# Power_Supply.net
KiCad netlist of a schematic drawn in Altium Designer
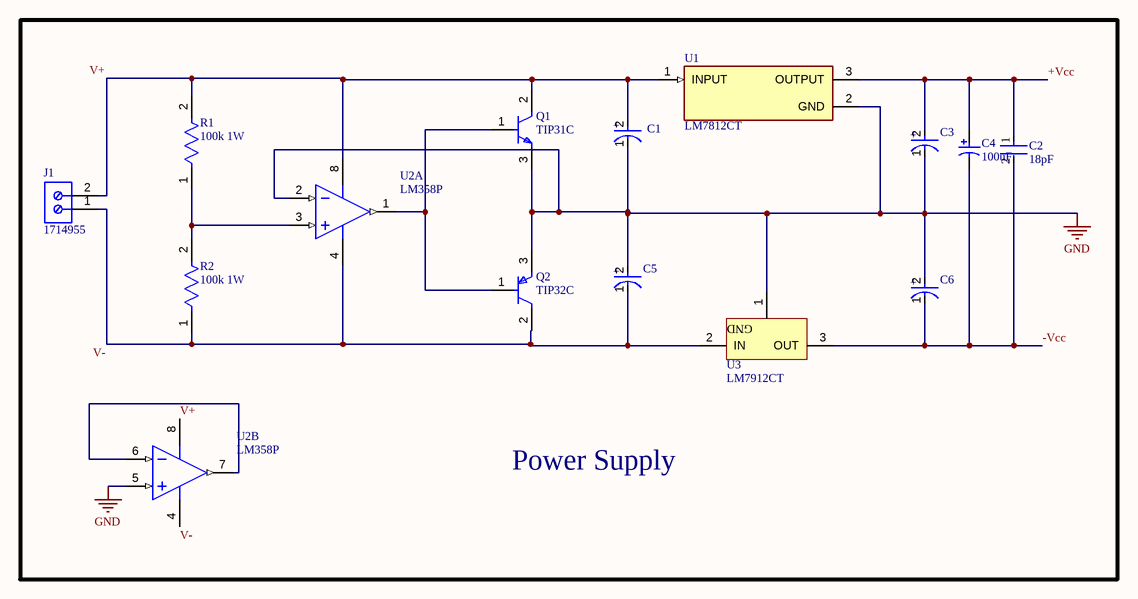
[diagram p0: Power_Supply.SchDoc]

(export (version "E")
  (design (tool "Eeschema 10.0.6"))
  (components
    (comp (ref "C1")
      (value "EEUFC1H4R7B")
      (footprint "FP-RAD-TH-D_5_0_5-L_11_1-MFG")
      (description "Aluminum Electrolytic Capacitors (Radial Lead Type) AEC-Q200 Qualified 4.7uF ±20% 50V")
      (fields (field (name "TOLERANCE") "20%"))
      (libsource (lib "Altium Content Vault") (part "a00bbbee19879c290e62620ae7e47b1"))
    )
    (comp (ref "C2")
      (value "18pF")
      (footprint "FP-F471K33Y5RP6UK5R-MFG")
      (description "CAP CER 470PF 2KV Y5R RADIAL")
      (fields (field (name "TOLERANCE") "10%") (field (name "VOLTAGE") "2kV"))
      (libsource (lib "Altium Content Vault") (part "b4654b650e69147ec39a6b967a45e02"))
    )
    (comp (ref "C3")
      (value "EEUFC1H4R7B")
      (footprint "FP-RAD-TH-D_5_0_5-L_11_1-MFG")
      (description "Aluminum Electrolytic Capacitors (Radial Lead Type) AEC-Q200 Qualified 4.7uF ±20% 50V")
      (fields (field (name "TOLERANCE") "20%"))
      (libsource (lib "Altium Content Vault") (part "a00bbbee19879c290e62620ae7e47b1"))
    )
    (comp (ref "C4")
      (value "100uF")
      (footprint "CAPPR65-350-1150X800X1250")
      (description "Aluminum Electrolytic Capacitor, 100 uF, +/- 20%, 50 V, -40 to 85 degC, 2-Pin THD, RoHS, Bulk")
      (fields (field (name "MANUFACTURER") "Panasonic") (field (name "VOLTAGE") "50V"))
      (libsource (lib "Altium Content Vault") (part "CAP-P-2"))
    )
    (comp (ref "C5")
      (value "EEUFC1H4R7B")
      (footprint "FP-RAD-TH-D_5_0_5-L_11_1-MFG")
      (description "Aluminum Electrolytic Capacitors (Radial Lead Type) AEC-Q200 Qualified 4.7uF ±20% 50V")
      (fields (field (name "TOLERANCE") "20%"))
      (libsource (lib "Altium Content Vault") (part "a00bbbee19879c290e62620ae7e47b1"))
    )
    (comp (ref "C6")
      (value "EEUFC1H4R7B")
      (footprint "FP-RAD-TH-D_5_0_5-L_11_1-MFG")
      (description "Aluminum Electrolytic Capacitors (Radial Lead Type) AEC-Q200 Qualified 4.7uF ±20% 50V")
      (fields (field (name "TOLERANCE") "20%"))
      (libsource (lib "Altium Content Vault") (part "a00bbbee19879c290e62620ae7e47b1"))
    )
    (comp (ref "J1")
      (value "1714955")
      (footprint "PHOE-1714955_V")
      (description "PC Terminal Block, Pitch 6.35 mm, 1 x 2 Position, Height 21.5 mm, Tail Lenght 5.1 mm, RoHS, Bulk")
      (fields (field (name "MANUFACTURER") "Phoenix Contact"))
      (libsource (lib "Altium Content Vault") (part "CN-1P-F-TB2"))
    )
    (comp (ref "Q1")
      (value "TIP31C")
      (footprint "FP-TO-220-P0A0015988-MFG")
      (description "TRANS NPN 100V 3A TO-220")
      (fields
        (field (name "OCTOPART") "https://octopart.com/tip31c-stmicroelectronics-15555")
        (field (name "MANUFACTURER") "STMicroelectronics")
      )
      (libsource (lib "Altium Content Vault") (part "1c57d9dae74fe2702546667b0e849db"))
    )
    (comp (ref "Q2")
      (value "TIP32C")
      (footprint "FP-TO-220-P0A0015988-MFG")
      (description "TRANS PNP 100V 3A TO-220")
      (fields
        (field (name "MANUFACTURER") "STMicroelectronics")
        (field (name "OCTOPART") "https://octopart.com/tip32c-stmicroelectronics-353617")
      )
      (libsource (lib "Altium Content Vault") (part "802a31d42ca070764d097f06bc9597f"))
    )
    (comp (ref "R1")
      (value "100k 1W")
      (footprint "FP-RR01-MFG")
      (description "RES 100K OHM 5% 1W AXIAL")
      (fields (field (name "TOLERANCE") "5%"))
      (libsource (lib "Altium Content Vault") (part "1029c3af85768c4190bb7ad29bc67b5"))
    )
    (comp (ref "R2")
      (value "100k 1W")
      (footprint "FP-RR01-MFG")
      (description "RES 100K OHM 5% 1W AXIAL")
      (fields (field (name "TOLERANCE") "5%"))
      (libsource (lib "Altium Content Vault") (part "1029c3af85768c4190bb7ad29bc67b5"))
    )
    (comp (ref "U1")
      (value "LM7812CT")
      (footprint "FP-TO220B03-MFG")
      (description "IC REG LINEAR 12V 1A TO220-3")
      (fields
        (field (name "OCTOPART") "https://octopart.com/lm7812ct-on+semiconductor-14383031")
        (field (name "OBSOLETE PART") "true")
      )
      (libsource (lib "Altium Content Vault") (part "6207a8f1a6b4db326a9e0a8a99b4969"))
    )
    (comp (ref "U2")
      (value "LM358P")
      (footprint "P0008A")
      (description "Dual Operational Amplifier, 3 to 32 V, 0 to 70 degC, 8-Pin PDIP (P), RoHS, Tape and Reel")
      (fields (field (name "MANUFACTURER") "Technik Industrial"))
      (libsource (lib "Altium Content Vault") (part "TI-LM_LPXXX-SO_DIP8"))
    )
    (comp (ref "U3")
      (value "LM7912CT")
      (footprint "NDE0003A")
      (description "3-Terminal Negative Regulator, 3-pin TO-220")
      (fields (field (name "MANUFACTURER") "Texas Instruments"))
      (libsource (lib "Altium Content Vault") (part "PM-REG-LM7905-SIL3"))
    )
  )
  (nets
    (net (code "1") (name "/+Vcc") (class "Default")
      (node (ref "C2") (pin "1") (pinfunction "1_1") (pintype "passive"))
      (node (ref "C3") (pin "2") (pinfunction "A_2") (pintype "passive"))
      (node (ref "C4") (pin "1") (pinfunction "1_1") (pintype "passive"))
      (node (ref "U1") (pin "3") (pinfunction "OUTPUT_3") (pintype "passive"))
    )
    (net (code "2") (name "/-Vcc") (class "Default")
      (node (ref "C2") (pin "2") (pinfunction "2_2") (pintype "passive"))
      (node (ref "C4") (pin "2") (pinfunction "2_2") (pintype "passive"))
      (node (ref "C6") (pin "1") (pinfunction "C_1") (pintype "passive"))
      (node (ref "U3") (pin "3") (pinfunction "OUT_3") (pintype "power_in"))
    )
    (net (code "3") (name "/V+") (class "Default")
      (node (ref "C1") (pin "2") (pinfunction "A_2") (pintype "passive"))
      (node (ref "J1") (pin "2") (pinfunction "2_2") (pintype "passive"))
      (node (ref "Q1") (pin "2") (pinfunction "C_2") (pintype "passive"))
      (node (ref "R1") (pin "2") (pinfunction "2_2") (pintype "passive"))
      (node (ref "U1") (pin "1") (pinfunction "INPUT_1") (pintype "input"))
      (node (ref "U2") (pin "8") (pinfunction "VCC_8") (pintype "power_in"))
    )
    (net (code "4") (name "/V-") (class "Default")
      (node (ref "C5") (pin "1") (pinfunction "C_1") (pintype "passive"))
      (node (ref "J1") (pin "1") (pinfunction "1_1") (pintype "passive"))
      (node (ref "Q2") (pin "2") (pinfunction "C_2") (pintype "passive"))
      (node (ref "R2") (pin "1") (pinfunction "1_1") (pintype "passive"))
      (node (ref "U2") (pin "4") (pinfunction "GND_4") (pintype "power_in"))
      (node (ref "U3") (pin "2") (pinfunction "IN_2") (pintype "power_in"))
    )
    (net (code "5") (name "GND") (class "Default")
      (node (ref "C1") (pin "1") (pinfunction "C_1") (pintype "passive"))
      (node (ref "C3") (pin "1") (pinfunction "C_1") (pintype "passive"))
      (node (ref "C5") (pin "2") (pinfunction "A_2") (pintype "passive"))
      (node (ref "C6") (pin "2") (pinfunction "A_2") (pintype "passive"))
      (node (ref "Q1") (pin "3") (pinfunction "E_3") (pintype "passive"))
      (node (ref "Q2") (pin "3") (pinfunction "E_3") (pintype "passive"))
      (node (ref "U1") (pin "2") (pinfunction "GND_2") (pintype "power_in"))
      (node (ref "U2") (pin "2") (pinfunction "1IN-_2") (pintype "input"))
      (node (ref "U2") (pin "5") (pinfunction "2IN+_5") (pintype "input"))
      (node (ref "U3") (pin "1") (pinfunction "GND_1") (pintype "power_in"))
    )
    (net (code "6") (name "Net-(Q1-B)") (class "Default")
      (node (ref "Q1") (pin "1") (pinfunction "B_1") (pintype "passive"))
      (node (ref "Q2") (pin "1") (pinfunction "B_1") (pintype "passive"))
      (node (ref "U2") (pin "1") (pinfunction "1OUT_1") (pintype "output"))
    )
    (net (code "7") (name "Net-(U2A-1IN+)") (class "Default")
      (node (ref "R1") (pin "1") (pinfunction "1_1") (pintype "passive"))
      (node (ref "R2") (pin "2") (pinfunction "2_2") (pintype "passive"))
      (node (ref "U2") (pin "3") (pinfunction "1IN+_3") (pintype "input"))
    )
    (net (code "8") (name "Net-(U2B-2IN-)") (class "Default")
      (node (ref "U2") (pin "6") (pinfunction "2IN-_6") (pintype "input"))
      (node (ref "U2") (pin "7") (pinfunction "2OUT_7") (pintype "output"))
    )
  )
)
